# pcb_Becker.net
KiCad netlist of a schematic drawn in EAGLE
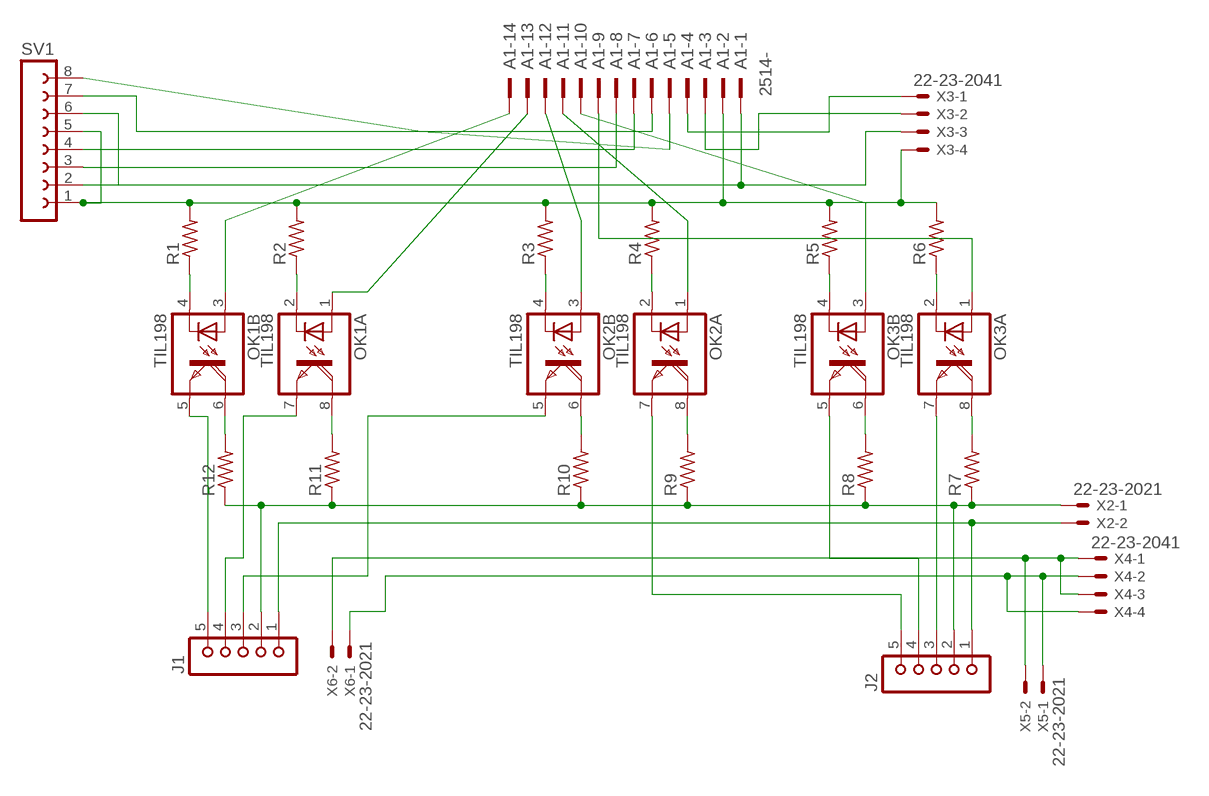
[diagram p0: schematic, sheet 1]

(export (version "E")
  (design (tool "Eeschema 10.0.6"))
  (components
    (comp (ref "A1")
      (value "2514-")
      (footprint "eagle-import:PAK100_2500-14")
      (libsource (lib "eagle-import") (part "2514-"))
    )
    (comp (ref "J1")
      (value "JU05")
      (footprint "eagle-import:JU05")
      (libsource (lib "eagle-import") (part "JU05"))
    )
    (comp (ref "J2")
      (value "JU05")
      (footprint "eagle-import:JU05")
      (libsource (lib "eagle-import") (part "JU05"))
    )
    (comp (ref "OK1")
      (value "TIL198")
      (footprint "eagle-import:DIL08")
      (libsource (lib "eagle-import") (part "TIL198"))
    )
    (comp (ref "OK2")
      (value "TIL198")
      (footprint "eagle-import:DIL08")
      (libsource (lib "eagle-import") (part "TIL198"))
    )
    (comp (ref "OK3")
      (value "TIL198")
      (footprint "eagle-import:DIL08")
      (libsource (lib "eagle-import") (part "TIL198"))
    )
    (comp (ref "R1")
      (value "R-US_0207/10")
      (footprint "eagle-import:0207_10")
      (libsource (lib "eagle-import") (part "R-US_0207/10"))
    )
    (comp (ref "R2")
      (value "R-US_0207/10")
      (footprint "eagle-import:0207_10")
      (libsource (lib "eagle-import") (part "R-US_0207/10"))
    )
    (comp (ref "R3")
      (value "R-US_0207/10")
      (footprint "eagle-import:0207_10")
      (libsource (lib "eagle-import") (part "R-US_0207/10"))
    )
    (comp (ref "R4")
      (value "R-US_0207/10")
      (footprint "eagle-import:0207_10")
      (libsource (lib "eagle-import") (part "R-US_0207/10"))
    )
    (comp (ref "R5")
      (value "R-US_0207/10")
      (footprint "eagle-import:0207_10")
      (libsource (lib "eagle-import") (part "R-US_0207/10"))
    )
    (comp (ref "R6")
      (value "R-US_0207/10")
      (footprint "eagle-import:0207_10")
      (libsource (lib "eagle-import") (part "R-US_0207/10"))
    )
    (comp (ref "R7")
      (value "R-US_0207/10")
      (footprint "eagle-import:0207_10")
      (libsource (lib "eagle-import") (part "R-US_0207/10"))
    )
    (comp (ref "R8")
      (value "R-US_0207/10")
      (footprint "eagle-import:0207_10")
      (libsource (lib "eagle-import") (part "R-US_0207/10"))
    )
    (comp (ref "R9")
      (value "R-US_0207/10")
      (footprint "eagle-import:0207_10")
      (libsource (lib "eagle-import") (part "R-US_0207/10"))
    )
    (comp (ref "R10")
      (value "R-US_0207/10")
      (footprint "eagle-import:0207_10")
      (libsource (lib "eagle-import") (part "R-US_0207/10"))
    )
    (comp (ref "R11")
      (value "R-US_0207/10")
      (footprint "eagle-import:0207_10")
      (libsource (lib "eagle-import") (part "R-US_0207/10"))
    )
    (comp (ref "R12")
      (value "R-US_0207/10")
      (footprint "eagle-import:0207_10")
      (libsource (lib "eagle-import") (part "R-US_0207/10"))
    )
    (comp (ref "SV1")
      (value "FE08-1")
      (footprint "eagle-import:FE08")
      (libsource (lib "eagle-import") (part "FE08-1"))
    )
    (comp (ref "X2")
      (value "22-23-2021")
      (footprint "eagle-import:22-23-2021")
      (fields (field (name "MF") "MOLEX"))
      (libsource (lib "eagle-import") (part "22-23-2021"))
    )
    (comp (ref "X3")
      (value "22-23-2041")
      (footprint "eagle-import:22-23-2041")
      (fields (field (name "MF") "MOLEX"))
      (libsource (lib "eagle-import") (part "22-23-2041"))
    )
    (comp (ref "X4")
      (value "22-23-2041")
      (footprint "eagle-import:22-23-2041")
      (fields (field (name "MF") "MOLEX"))
      (libsource (lib "eagle-import") (part "22-23-2041"))
    )
    (comp (ref "X5")
      (value "22-23-2021")
      (footprint "eagle-import:22-23-2021")
      (fields (field (name "MF") "MOLEX"))
      (libsource (lib "eagle-import") (part "22-23-2021"))
    )
    (comp (ref "X6")
      (value "22-23-2021")
      (footprint "eagle-import:22-23-2021")
      (fields (field (name "MF") "MOLEX"))
      (libsource (lib "eagle-import") (part "22-23-2021"))
    )
  )
  (nets
    (net (code "1") (name "Net-(A1A-KL)") (class "Default")
      (node (ref "A1") (pin "1") (pinfunction "KL_1") (pintype "passive"))
      (node (ref "SV1") (pin "2") (pinfunction "2_2") (pintype "passive"))
      (node (ref "SV1") (pin "6") (pinfunction "6_6") (pintype "passive"))
      (node (ref "X3") (pin "3") (pinfunction "S_3") (pintype "passive"))
    )
    (net (code "2") (name "Net-(A1B-KL)") (class "Default")
      (node (ref "A1") (pin "10") (pinfunction "KL_10") (pintype "passive"))
      (node (ref "OK3") (pin "3") (pinfunction "A_3") (pintype "passive"))
    )
    (net (code "3") (name "Net-(A1C-KL)") (class "Default")
      (node (ref "A1") (pin "11") (pinfunction "KL_11") (pintype "passive"))
      (node (ref "OK2") (pin "1") (pinfunction "A_1") (pintype "passive"))
    )
    (net (code "4") (name "Net-(A1D-KL)") (class "Default")
      (node (ref "A1") (pin "12") (pinfunction "KL_12") (pintype "passive"))
      (node (ref "OK2") (pin "3") (pinfunction "A_3") (pintype "passive"))
    )
    (net (code "5") (name "Net-(A1E-KL)") (class "Default")
      (node (ref "A1") (pin "13") (pinfunction "KL_13") (pintype "passive"))
      (node (ref "OK1") (pin "1") (pinfunction "A_1") (pintype "passive"))
    )
    (net (code "6") (name "Net-(A1F-KL)") (class "Default")
      (node (ref "A1") (pin "14") (pinfunction "KL_14") (pintype "passive"))
      (node (ref "OK1") (pin "3") (pinfunction "A_3") (pintype "passive"))
    )
    (net (code "7") (name "Net-(A1G-KL)") (class "Default")
      (node (ref "A1") (pin "2") (pinfunction "KL_2") (pintype "passive"))
      (node (ref "R1") (pin "2") (pinfunction "2_2") (pintype "passive"))
      (node (ref "R2") (pin "2") (pinfunction "2_2") (pintype "passive"))
      (node (ref "R3") (pin "2") (pinfunction "2_2") (pintype "passive"))
      (node (ref "R4") (pin "2") (pinfunction "2_2") (pintype "passive"))
      (node (ref "R5") (pin "2") (pinfunction "2_2") (pintype "passive"))
      (node (ref "R6") (pin "2") (pinfunction "2_2") (pintype "passive"))
      (node (ref "SV1") (pin "1") (pinfunction "1_1") (pintype "passive"))
      (node (ref "SV1") (pin "5") (pinfunction "5_5") (pintype "passive"))
      (node (ref "X3") (pin "4") (pinfunction "S_4") (pintype "passive"))
    )
    (net (code "8") (name "Net-(A1H-KL)") (class "Default")
      (node (ref "A1") (pin "3") (pinfunction "KL_3") (pintype "passive"))
      (node (ref "X3") (pin "2") (pinfunction "S_2") (pintype "passive"))
    )
    (net (code "9") (name "Net-(A1I-KL)") (class "Default")
      (node (ref "A1") (pin "4") (pinfunction "KL_4") (pintype "passive"))
      (node (ref "X3") (pin "1") (pinfunction "S_1") (pintype "passive"))
    )
    (net (code "10") (name "Net-(A1J-KL)") (class "Default")
      (node (ref "A1") (pin "5") (pinfunction "KL_5") (pintype "passive"))
      (node (ref "SV1") (pin "8") (pinfunction "8_8") (pintype "passive"))
    )
    (net (code "11") (name "Net-(A1K-KL)") (class "Default")
      (node (ref "A1") (pin "6") (pinfunction "KL_6") (pintype "passive"))
      (node (ref "SV1") (pin "7") (pinfunction "7_7") (pintype "passive"))
    )
    (net (code "12") (name "Net-(A1L-KL)") (class "Default")
      (node (ref "A1") (pin "7") (pinfunction "KL_7") (pintype "passive"))
      (node (ref "SV1") (pin "4") (pinfunction "4_4") (pintype "passive"))
    )
    (net (code "13") (name "Net-(A1M-KL)") (class "Default")
      (node (ref "A1") (pin "8") (pinfunction "KL_8") (pintype "passive"))
      (node (ref "SV1") (pin "3") (pinfunction "3_3") (pintype "passive"))
    )
    (net (code "14") (name "Net-(A1N-KL)") (class "Default")
      (node (ref "A1") (pin "9") (pinfunction "KL_9") (pintype "passive"))
      (node (ref "OK3") (pin "1") (pinfunction "A_1") (pintype "passive"))
    )
    (net (code "15") (name "Net-(OK1A-C)") (class "Default")
      (node (ref "OK1") (pin "2") (pinfunction "C_2") (pintype "passive"))
      (node (ref "R2") (pin "1") (pinfunction "1_1") (pintype "passive"))
    )
    (net (code "16") (name "Net-(OK1A-COL)") (class "Default")
      (node (ref "OK1") (pin "8") (pinfunction "COL_8") (pintype "passive"))
      (node (ref "R11") (pin "2") (pinfunction "2_2") (pintype "passive"))
    )
    (net (code "17") (name "Net-(OK1A-EMI)") (class "Default")
      (node (ref "J1") (pin "4") (pinfunction "4_4") (pintype "passive"))
      (node (ref "OK1") (pin "7") (pinfunction "EMI_7") (pintype "passive"))
    )
    (net (code "18") (name "Net-(OK1B-C)") (class "Default")
      (node (ref "OK1") (pin "4") (pinfunction "C_4") (pintype "passive"))
      (node (ref "R1") (pin "1") (pinfunction "1_1") (pintype "passive"))
    )
    (net (code "19") (name "Net-(OK1B-COL)") (class "Default")
      (node (ref "OK1") (pin "6") (pinfunction "COL_6") (pintype "passive"))
      (node (ref "R12") (pin "2") (pinfunction "2_2") (pintype "passive"))
    )
    (net (code "20") (name "Net-(OK1B-EMI)") (class "Default")
      (node (ref "J1") (pin "5") (pinfunction "5_5") (pintype "passive"))
      (node (ref "OK1") (pin "5") (pinfunction "EMI_5") (pintype "passive"))
    )
    (net (code "21") (name "Net-(OK2A-C)") (class "Default")
      (node (ref "OK2") (pin "2") (pinfunction "C_2") (pintype "passive"))
      (node (ref "R4") (pin "1") (pinfunction "1_1") (pintype "passive"))
    )
    (net (code "22") (name "Net-(OK2A-COL)") (class "Default")
      (node (ref "OK2") (pin "8") (pinfunction "COL_8") (pintype "passive"))
      (node (ref "R9") (pin "2") (pinfunction "2_2") (pintype "passive"))
    )
    (net (code "23") (name "Net-(OK2A-EMI)") (class "Default")
      (node (ref "J2") (pin "5") (pinfunction "5_5") (pintype "passive"))
      (node (ref "OK2") (pin "7") (pinfunction "EMI_7") (pintype "passive"))
    )
    (net (code "24") (name "Net-(OK2B-C)") (class "Default")
      (node (ref "OK2") (pin "4") (pinfunction "C_4") (pintype "passive"))
      (node (ref "R3") (pin "1") (pinfunction "1_1") (pintype "passive"))
    )
    (net (code "25") (name "Net-(OK2B-COL)") (class "Default")
      (node (ref "OK2") (pin "6") (pinfunction "COL_6") (pintype "passive"))
      (node (ref "R10") (pin "2") (pinfunction "2_2") (pintype "passive"))
    )
    (net (code "26") (name "Net-(OK2B-EMI)") (class "Default")
      (node (ref "J1") (pin "3") (pinfunction "3_3") (pintype "passive"))
      (node (ref "OK2") (pin "5") (pinfunction "EMI_5") (pintype "passive"))
    )
    (net (code "27") (name "Net-(OK3A-C)") (class "Default")
      (node (ref "OK3") (pin "2") (pinfunction "C_2") (pintype "passive"))
      (node (ref "R6") (pin "1") (pinfunction "1_1") (pintype "passive"))
    )
    (net (code "28") (name "Net-(OK3A-COL)") (class "Default")
      (node (ref "OK3") (pin "8") (pinfunction "COL_8") (pintype "passive"))
      (node (ref "R7") (pin "2") (pinfunction "2_2") (pintype "passive"))
    )
    (net (code "29") (name "Net-(OK3A-EMI)") (class "Default")
      (node (ref "J2") (pin "3") (pinfunction "3_3") (pintype "passive"))
      (node (ref "OK3") (pin "7") (pinfunction "EMI_7") (pintype "passive"))
    )
    (net (code "30") (name "Net-(OK3B-C)") (class "Default")
      (node (ref "OK3") (pin "4") (pinfunction "C_4") (pintype "passive"))
      (node (ref "R5") (pin "1") (pinfunction "1_1") (pintype "passive"))
    )
    (net (code "31") (name "Net-(OK3B-COL)") (class "Default")
      (node (ref "OK3") (pin "6") (pinfunction "COL_6") (pintype "passive"))
      (node (ref "R8") (pin "2") (pinfunction "2_2") (pintype "passive"))
    )
    (net (code "32") (name "Net-(OK3B-EMI)") (class "Default")
      (node (ref "J2") (pin "4") (pinfunction "4_4") (pintype "passive"))
      (node (ref "OK3") (pin "5") (pinfunction "EMI_5") (pintype "passive"))
    )
    (net (code "33") (name "Net-(X2A-S)") (class "Default")
      (node (ref "J1") (pin "2") (pinfunction "2_2") (pintype "passive"))
      (node (ref "J2") (pin "2") (pinfunction "2_2") (pintype "passive"))
      (node (ref "R10") (pin "1") (pinfunction "1_1") (pintype "passive"))
      (node (ref "R11") (pin "1") (pinfunction "1_1") (pintype "passive"))
      (node (ref "R12") (pin "1") (pinfunction "1_1") (pintype "passive"))
      (node (ref "R7") (pin "1") (pinfunction "1_1") (pintype "passive"))
      (node (ref "R8") (pin "1") (pinfunction "1_1") (pintype "passive"))
      (node (ref "R9") (pin "1") (pinfunction "1_1") (pintype "passive"))
      (node (ref "X2") (pin "1") (pinfunction "S_1") (pintype "passive"))
    )
    (net (code "34") (name "Net-(X2B-S)") (class "Default")
      (node (ref "J1") (pin "1") (pinfunction "1_1") (pintype "passive"))
      (node (ref "J2") (pin "1") (pinfunction "1_1") (pintype "passive"))
      (node (ref "X2") (pin "2") (pinfunction "S_2") (pintype "passive"))
    )
    (net (code "35") (name "Net-(X4A-S)") (class "Default")
      (node (ref "X4") (pin "1") (pinfunction "S_1") (pintype "passive"))
      (node (ref "X4") (pin "3") (pinfunction "S_3") (pintype "passive"))
      (node (ref "X5") (pin "2") (pinfunction "S_2") (pintype "passive"))
      (node (ref "X6") (pin "2") (pinfunction "S_2") (pintype "passive"))
    )
    (net (code "36") (name "Net-(X4B-S)") (class "Default")
      (node (ref "X4") (pin "2") (pinfunction "S_2") (pintype "passive"))
      (node (ref "X4") (pin "4") (pinfunction "S_4") (pintype "passive"))
      (node (ref "X5") (pin "1") (pinfunction "S_1") (pintype "passive"))
      (node (ref "X6") (pin "1") (pinfunction "S_1") (pintype "passive"))
    )
  )
)
